# RELAY_12VV_VDD_LEVEL.net
KiCad netlist of a schematic drawn in Altium Designer
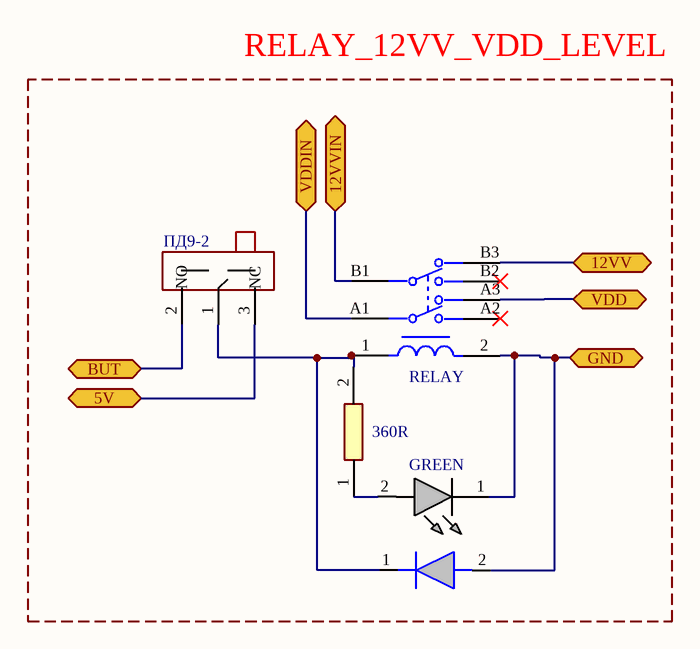
[diagram p0: RELAY_12VV_VDD_LEVEL.SchDoc]

(export (version "E")
  (design (tool "Eeschema 10.0.6"))
  (components
    (comp (ref "DIODRELE1")
      (value "DIOD0805")
      (footprint "DIOD0805")
      (description "1N4448WS-7-F")
      (libsource (lib "Components_Robots") (part "DIOD0805"))
    )
    (comp (ref "LEDRELE1")
      (value "GREEN")
      (footprint "LED0805")
      (description "LED-SMD0805")
      (libsource (lib "Components_Robots") (part "LED0805"))
    )
    (comp (ref "RELAY1")
      (value "RELAY")
      (footprint "RELAY-5V")
      (description "R2G2CH005")
      (libsource (lib "Components_Robots") (part "RELAY-5V"))
    )
    (comp (ref "RESRELE1")
      (value "360R")
      (footprint "RES0805")
      (description "RES-SMD0805")
      (libsource (lib "Components_Robots") (part "RES0805"))
    )
    (comp (ref "ПД9-2RELE2")
      (value "ПД9-2")
      (footprint "ПД9-2")
      (libsource (lib "Components_Robots") (part "ПД9-2"))
    )
  )
  (nets
    (net (code "1") (name "/5V") (class "Default")
      (node (ref "ПД9-2RELE2") (pin "3") (pinfunction "NC_3") (pintype "passive"))
    )
    (net (code "2") (name "/12VV") (class "Default")
      (node (ref "RELAY1") (pin "B3") (pinfunction "22_B3") (pintype "passive"))
    )
    (net (code "3") (name "/12VVIN") (class "Default")
      (node (ref "RELAY1") (pin "B1") (pinfunction "21_B1") (pintype "passive"))
    )
    (net (code "4") (name "/BUT") (class "Default")
      (node (ref "ПД9-2RELE2") (pin "2") (pinfunction "NO_2") (pintype "passive"))
    )
    (net (code "5") (name "/GND") (class "Default")
      (node (ref "DIODRELE1") (pin "2") (pinfunction "A_2") (pintype "passive"))
      (node (ref "LEDRELE1") (pin "1") (pinfunction "K_1") (pintype "passive"))
      (node (ref "RELAY1") (pin "2") (pinfunction "A2_2") (pintype "passive"))
    )
    (net (code "6") (name "/VDD") (class "Default")
      (node (ref "RELAY1") (pin "A3") (pinfunction "12_A3") (pintype "passive"))
    )
    (net (code "7") (name "/VDDIN") (class "Default")
      (node (ref "RELAY1") (pin "A1") (pinfunction "11_A1") (pintype "passive"))
    )
    (net (code "8") (name "Net-(DIODRELE1-K)") (class "Default")
      (node (ref "DIODRELE1") (pin "1") (pinfunction "K_1") (pintype "passive"))
      (node (ref "RELAY1") (pin "1") (pinfunction "A1_1") (pintype "passive"))
      (node (ref "RESRELE1") (pin "2") (pinfunction "2_2") (pintype "passive"))
      (node (ref "ПД9-2RELE2") (pin "1") (pinfunction "COM_1") (pintype "passive"))
    )
    (net (code "9") (name "Net-(LEDRELE1-A)") (class "Default")
      (node (ref "LEDRELE1") (pin "2") (pinfunction "A_2") (pintype "passive"))
      (node (ref "RESRELE1") (pin "1") (pinfunction "1_1") (pintype "passive"))
    )
    (net (code "10") (name "unconnected-(RELAY1-14-PadA2)") (class "Default")
      (node (ref "RELAY1") (pin "A2") (pinfunction "14_A2") (pintype "passive+no_connect"))
    )
    (net (code "11") (name "unconnected-(RELAY1-24-PadB2)") (class "Default")
      (node (ref "RELAY1") (pin "B2") (pinfunction "24_B2") (pintype "passive+no_connect"))
    )
  )
)
